# ControlRadio.net
KiCad netlist of a schematic drawn in Altium Designer
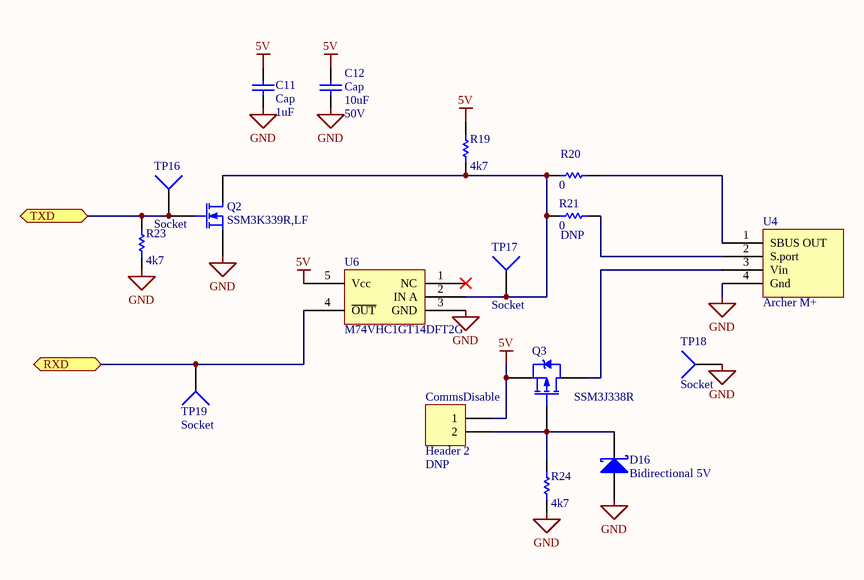
[diagram p0: ControlRadio.SchDoc]

(export (version "E")
  (design (tool "Eeschema 10.0.6"))
  (components
    (comp (ref "C11")
      (value "Cap")
      (footprint "RESC3116X65N")
      (description "Capacitor")
      (fields
        (field (name "ALTIUM_VALUE") "1uF")
        (field (name "MANUFACTURER PART NUMBER") "CL31B105KCHNNNE")
        (field (name "VENDOR PART NUMBER") "1276-1838-1-ND")
      )
      (libsource (lib "Miscellaneous Devices") (part "Cap"))
    )
    (comp (ref "C12")
      (value "Cap")
      (footprint "CAPC3216X180N")
      (description "Capacitor")
      (fields
        (field (name "ALTIUM_VALUE") "10uF")
        (field (name "MANUFACTURER PART NUMBER") "CL31A106MBHNNNE")
        (field (name "VENDOR PART NUMBER") "1276-6736-1-ND")
        (field (name "VOLTAGE RATING") "50V")
      )
      (libsource (lib "Miscellaneous Devices") (part "Cap"))
    )
    (comp (ref "CommsDisable")
      (value "Header 2")
      (footprint "HDR1X2")
      (description "Header, 2-Pin")
      (fields (field (name "DNP") "DNP") (field (name "PUBLISHER") "Altium Limited"))
      (libsource (lib "Miscellaneous Connectors") (part "Header 2"))
    )
    (comp (ref "D16")
      (value "Bidirectional 5V")
      (footprint "THRMC0603X33N")
      (description "TVS")
      (fields
        (field (name "MANUFACTURER PART NUMBER") "CPDUC5V0R-HF")
        (field (name "VENDOR PART NUMBER") "641-1764-1-ND")
      )
      (libsource (lib "Miscellaneous Devices") (part "Diode 10TQ040"))
    )
    (comp (ref "Q2")
      (value "SSM3K339R,LF")
      (footprint "SOT95P237X112-3N")
      (description "N-Channel MOSFET")
      (fields (field (name "VENDOR PART NUMBER") "SSM3K339RLFCT-ND"))
      (libsource (lib "Miscellaneous Devices") (part "MOSFET-N"))
    )
    (comp (ref "Q3")
      (value "SSM3J338R")
      (footprint "SOT95P237X112-3N")
      (description "P-Channel Power MOSFET")
      (fields (field (name "VENDOR PART NUMBER") "SSM3J338RLFCT-ND"))
      (libsource (lib "Miscellaneous Devices") (part "PMOS-2"))
    )
    (comp (ref "R19")
      (value "4k7")
      (footprint "0402")
      (description "Resistor")
      (fields
        (field (name "MANUFACTURER PART NUMBER") "RC0402FR-074K7L")
        (field (name "VENDOR PART NUMBER") "311-4.7KLRCT-ND")
      )
      (libsource (lib "Miscellaneous Devices") (part "Res1"))
    )
    (comp (ref "R20")
      (value "0")
      (footprint "0402")
      (description "Resistor")
      (fields
        (field (name "MANUFACTURER PART NUMBER") "RC0402FR-070RL")
        (field (name "VENDOR PART NUMBER") "311-0.0LRCT-ND")
      )
      (libsource (lib "Miscellaneous Devices") (part "Res1"))
    )
    (comp (ref "R21")
      (value "0")
      (footprint "0402")
      (description "Resistor")
      (fields
        (field (name "MANUFACTURER PART NUMBER") "RC0402FR-070RL")
        (field (name "VENDOR PART NUMBER") "311-0.0LRCT-ND")
        (field (name "DNP") "DNP")
      )
      (libsource (lib "Miscellaneous Devices") (part "Res1"))
    )
    (comp (ref "R23")
      (value "4k7")
      (footprint "0402")
      (description "Resistor")
      (fields
        (field (name "MANUFACTURER PART NUMBER") "RC0402FR-074K7L")
        (field (name "VENDOR PART NUMBER") "311-4.7KLRCT-ND")
      )
      (libsource (lib "Miscellaneous Devices") (part "Res1"))
    )
    (comp (ref "R24")
      (value "4k7")
      (footprint "0402")
      (description "Resistor")
      (fields
        (field (name "MANUFACTURER PART NUMBER") "RC0402FR-074K7L")
        (field (name "VENDOR PART NUMBER") "311-4.7KLRCT-ND")
      )
      (libsource (lib "Miscellaneous Devices") (part "Res1"))
    )
    (comp (ref "TP16")
      (value "Socket")
      (footprint "5006")
      (fields
        (field (name "MANUFACTURER PART NUMBER") "5006")
        (field (name "VENDOR PART NUMBER") "36-5006-ND")
        (field (name "PUBLISHER") "Altium Limited")
      )
      (libsource (lib "Miscellaneous Connectors") (part "Socket"))
    )
    (comp (ref "TP17")
      (value "Socket")
      (footprint "5006")
      (fields
        (field (name "MANUFACTURER PART NUMBER") "5006")
        (field (name "VENDOR PART NUMBER") "36-5006-ND")
        (field (name "PUBLISHER") "Altium Limited")
      )
      (libsource (lib "Miscellaneous Connectors") (part "Socket"))
    )
    (comp (ref "TP18")
      (value "Socket")
      (footprint "5006")
      (fields
        (field (name "MANUFACTURER PART NUMBER") "5006")
        (field (name "VENDOR PART NUMBER") "36-5006-ND")
        (field (name "PUBLISHER") "Altium Limited")
      )
      (libsource (lib "Miscellaneous Connectors") (part "Socket"))
    )
    (comp (ref "TP19")
      (value "Socket")
      (footprint "5006")
      (fields
        (field (name "MANUFACTURER PART NUMBER") "5006")
        (field (name "VENDOR PART NUMBER") "36-5006-ND")
        (field (name "PUBLISHER") "Altium Limited")
      )
      (libsource (lib "Miscellaneous Connectors") (part "Socket"))
    )
    (comp (ref "U4")
      (value "Archer M+")
      (footprint "Archer M+")
      (fields (field (name "VENDOR PART NUMBER") "Archer +"))
      (libsource (lib "BeagleCape") (part "Archer M+"))
    )
    (comp (ref "U6")
      (value "M74VHC1GT14DFT2G")
      (footprint "SOT65P210X110-5N")
      (fields (field (name "VENDOR PART NUMBER") "M74VHC1GT14DFT2GOSCT-ND"))
      (libsource (lib "BeagleCape") (part "M74VHC1GT14DFT2G"))
    )
  )
  (nets
    (net (code "1") (name "/RXD") (class "Default")
      (node (ref "TP19") (pin "1") (pinfunction "1_1") (pintype "passive"))
      (node (ref "U6") (pin "4") (pinfunction "~{OUT}_4") (pintype "passive"))
    )
    (net (code "2") (name "/TXD") (class "Default")
      (node (ref "Q2") (pin "1") (pinfunction "G_1") (pintype "passive"))
      (node (ref "R23") (pin "1") (pinfunction "1_1") (pintype "passive"))
      (node (ref "TP16") (pin "1") (pinfunction "1_1") (pintype "passive"))
    )
    (net (code "3") (name "5V") (class "Default")
      (node (ref "C11") (pin "2") (pinfunction "2_2") (pintype "passive"))
      (node (ref "C12") (pin "2") (pinfunction "2_2") (pintype "passive"))
      (node (ref "CommsDisable") (pin "1") (pinfunction "1_1") (pintype "passive"))
      (node (ref "Q3") (pin "2") (pinfunction "S_2") (pintype "passive"))
      (node (ref "R19") (pin "1") (pinfunction "1_1") (pintype "passive"))
      (node (ref "U6") (pin "5") (pinfunction "Vcc_5") (pintype "passive"))
    )
    (net (code "4") (name "GND") (class "Default")
      (node (ref "C11") (pin "1") (pinfunction "1_1") (pintype "passive"))
      (node (ref "C12") (pin "1") (pinfunction "1_1") (pintype "passive"))
      (node (ref "D16") (pin "3") (pinfunction "A_3") (pintype "passive"))
      (node (ref "Q2") (pin "2") (pinfunction "S_2") (pintype "passive"))
      (node (ref "R23") (pin "2") (pinfunction "2_2") (pintype "passive"))
      (node (ref "R24") (pin "2") (pinfunction "2_2") (pintype "passive"))
      (node (ref "TP18") (pin "1") (pinfunction "1_1") (pintype "passive"))
      (node (ref "U4") (pin "4") (pinfunction "Gnd_4") (pintype "passive"))
      (node (ref "U6") (pin "3") (pinfunction "GND_3") (pintype "passive"))
    )
    (net (code "5") (name "Net-(D16-K)") (class "Default")
      (node (ref "CommsDisable") (pin "2") (pinfunction "2_2") (pintype "passive"))
      (node (ref "D16") (pin "1") (pinfunction "K_1") (pintype "passive"))
      (node (ref "Q3") (pin "1") (pinfunction "G_1") (pintype "passive"))
      (node (ref "R24") (pin "1") (pinfunction "1_1") (pintype "passive"))
    )
    (net (code "6") (name "Net-(Q2-D)") (class "Default")
      (node (ref "Q2") (pin "3") (pinfunction "D_3") (pintype "passive"))
      (node (ref "R19") (pin "2") (pinfunction "2_2") (pintype "passive"))
      (node (ref "R20") (pin "1") (pinfunction "1_1") (pintype "passive"))
      (node (ref "R21") (pin "1") (pinfunction "1_1") (pintype "passive"))
      (node (ref "TP17") (pin "1") (pinfunction "1_1") (pintype "passive"))
      (node (ref "U6") (pin "2") (pinfunction "IN_A_2") (pintype "passive"))
    )
    (net (code "7") (name "Net-(Q3-D)") (class "Default")
      (node (ref "Q3") (pin "3") (pinfunction "D_3") (pintype "passive"))
      (node (ref "U4") (pin "3") (pinfunction "Vin_3") (pintype "passive"))
    )
    (net (code "8") (name "Net-(U4-S.port)") (class "Default")
      (node (ref "R21") (pin "2") (pinfunction "2_2") (pintype "passive"))
      (node (ref "U4") (pin "2") (pinfunction "S.port_2") (pintype "passive"))
    )
    (net (code "9") (name "Net-(U4-SBUS_OUT)") (class "Default")
      (node (ref "R20") (pin "2") (pinfunction "2_2") (pintype "passive"))
      (node (ref "U4") (pin "1") (pinfunction "SBUS_OUT_1") (pintype "passive"))
    )
    (net (code "10") (name "unconnected-(U6-NC-Pad1)") (class "Default")
      (node (ref "U6") (pin "1") (pinfunction "NC_1") (pintype "passive+no_connect"))
    )
  )
)
